# Relay.net
KiCad netlist of a schematic drawn in Altium Designer
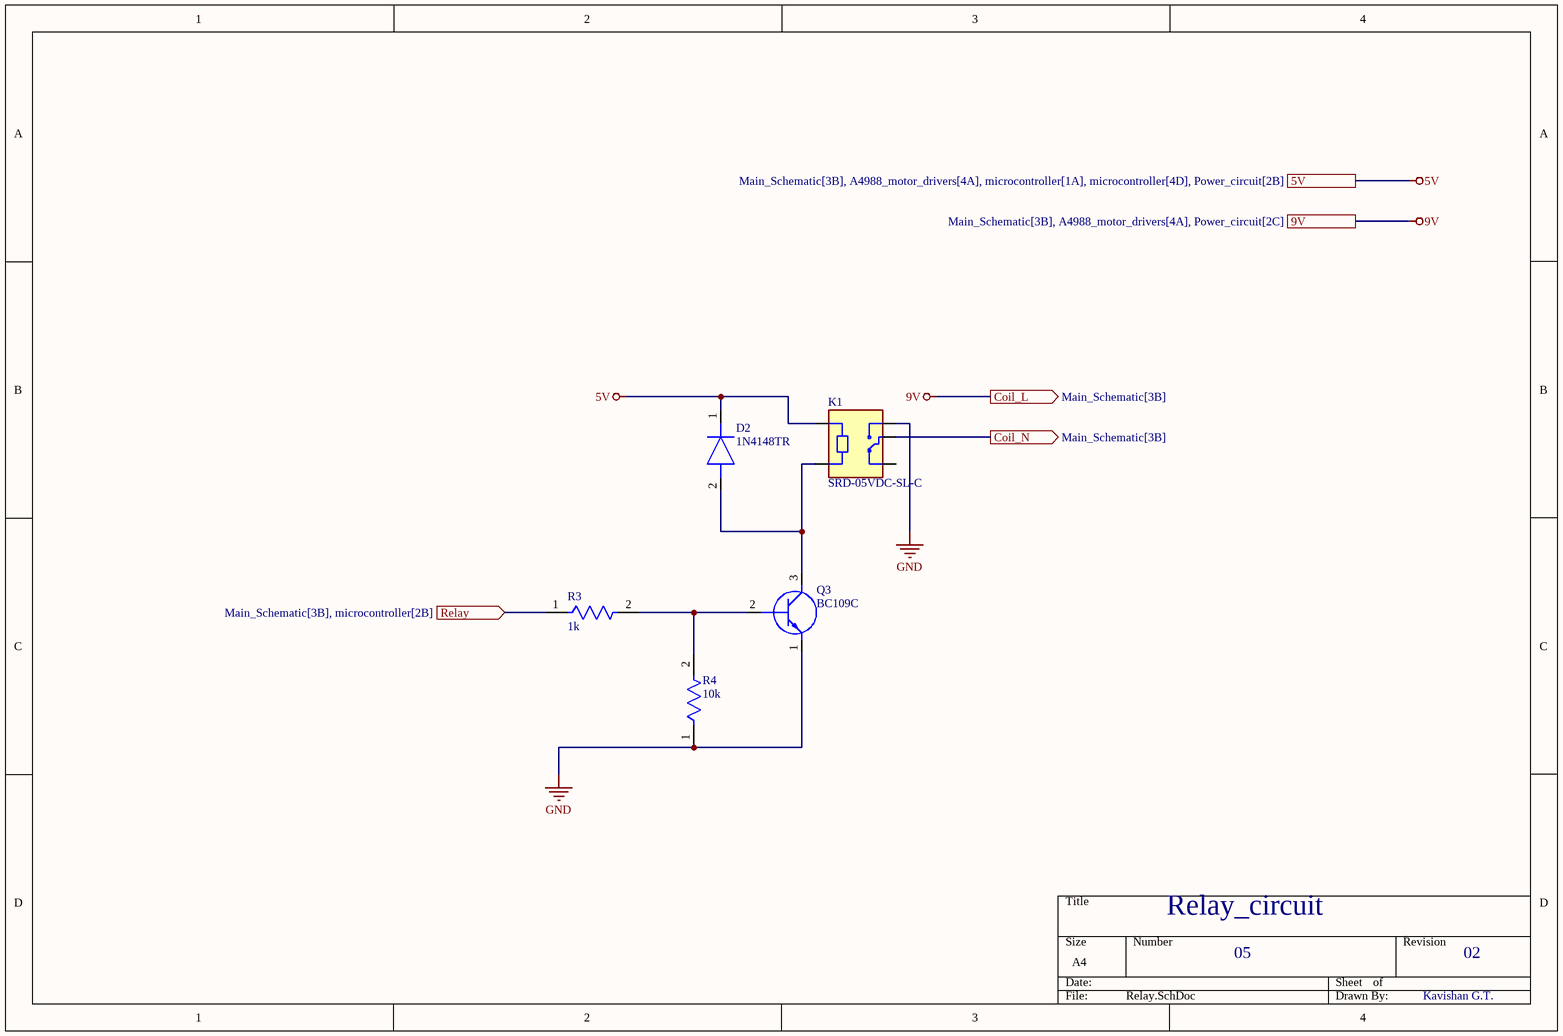
[diagram p0: Relay.SchDoc]

(export (version "E")
  (design (tool "Eeschema 10.0.6"))
  (components
    (comp (ref "D2")
      (value "1N4148TR")
      (footprint "SamacSys:DIOAD990W55L340D162")
      (description "Diode")
      (fields (field (name "MOUSER PART NUMBER") "78-1N4148"))
      (libsource (lib "*") (part "1N4148TR"))
    )
    (comp (ref "K1")
      (value "SRD-05VDC-SL-C")
      (footprint "RELAY_SRD-05VDC-SL-C")
      (fields (field (name "MF") "Songle Relay"))
      (libsource (lib "SRD-05VDC-SL-C") (part "SRD-05VDC-SL-C"))
    )
    (comp (ref "Q3")
      (value "BC109C")
      (footprint "SamacSys:CENTRAL_TO18")
      (description "Transistor BJT NPN")
      (fields (field (name "MOUSER PART NUMBER") "610-BC109C"))
      (libsource (lib "*") (part "BC109C"))
    )
    (comp (ref "R3")
      (value "1k")
      (footprint "FP-MFR-25-MFG")
      (description "RES 1.18K OHM 1/4W 1% AXIAL")
      (fields (field (name "MANUFACTURER") "Yageo") (field (name "TOLERANCE") "1%"))
      (libsource (lib "Altium Content Vault") (part "1029c3af85768c4190bb7ad29bc67b5"))
    )
    (comp (ref "R4")
      (value "10k")
      (footprint "FP-MFR-25-MFG")
      (description "RES 1.18K OHM 1/4W 1% AXIAL")
      (fields (field (name "MANUFACTURER") "Yageo") (field (name "TOLERANCE") "1%"))
      (libsource (lib "Altium Content Vault") (part "1029c3af85768c4190bb7ad29bc67b5"))
    )
  )
  (nets
    (net (code "1") (name "/Coil_N") (class "Default")
      (node (ref "K1") (pin "COM") (pinfunction "COM_COM") (pintype "passive"))
    )
    (net (code "2") (name "/Relay") (class "Default")
      (node (ref "R3") (pin "1") (pinfunction "1_1") (pintype "passive"))
    )
    (net (code "3") (name "5V") (class "Default")
      (node (ref "D2") (pin "1") (pinfunction "K_1") (pintype "passive"))
      (node (ref "K1") (pin "A1") (pinfunction "A1_A1") (pintype "passive"))
    )
    (net (code "5") (name "GND") (class "Default")
      (node (ref "K1") (pin "NO") (pinfunction "NO_NO") (pintype "passive"))
      (node (ref "Q3") (pin "1") (pinfunction "E_1") (pintype "passive"))
      (node (ref "R4") (pin "1") (pinfunction "1_1") (pintype "passive"))
    )
    (net (code "6") (name "Net-(D2-A)") (class "Default")
      (node (ref "D2") (pin "2") (pinfunction "A_2") (pintype "passive"))
      (node (ref "K1") (pin "A2") (pinfunction "A2_A2") (pintype "passive"))
      (node (ref "Q3") (pin "3") (pinfunction "C_3") (pintype "passive"))
    )
    (net (code "7") (name "Net-(Q3-B)") (class "Default")
      (node (ref "Q3") (pin "2") (pinfunction "B_2") (pintype "passive"))
      (node (ref "R3") (pin "2") (pinfunction "2_2") (pintype "passive"))
      (node (ref "R4") (pin "2") (pinfunction "2_2") (pintype "passive"))
    )
    (net (code "8") (name "unconnected-(K1-PadNC)") (class "Default")
      (node (ref "K1") (pin "NC") (pinfunction "NC_NC") (pintype "passive"))
    )
  )
)
